# PoppingUnit.net
KiCad netlist of a schematic drawn in EAGLE
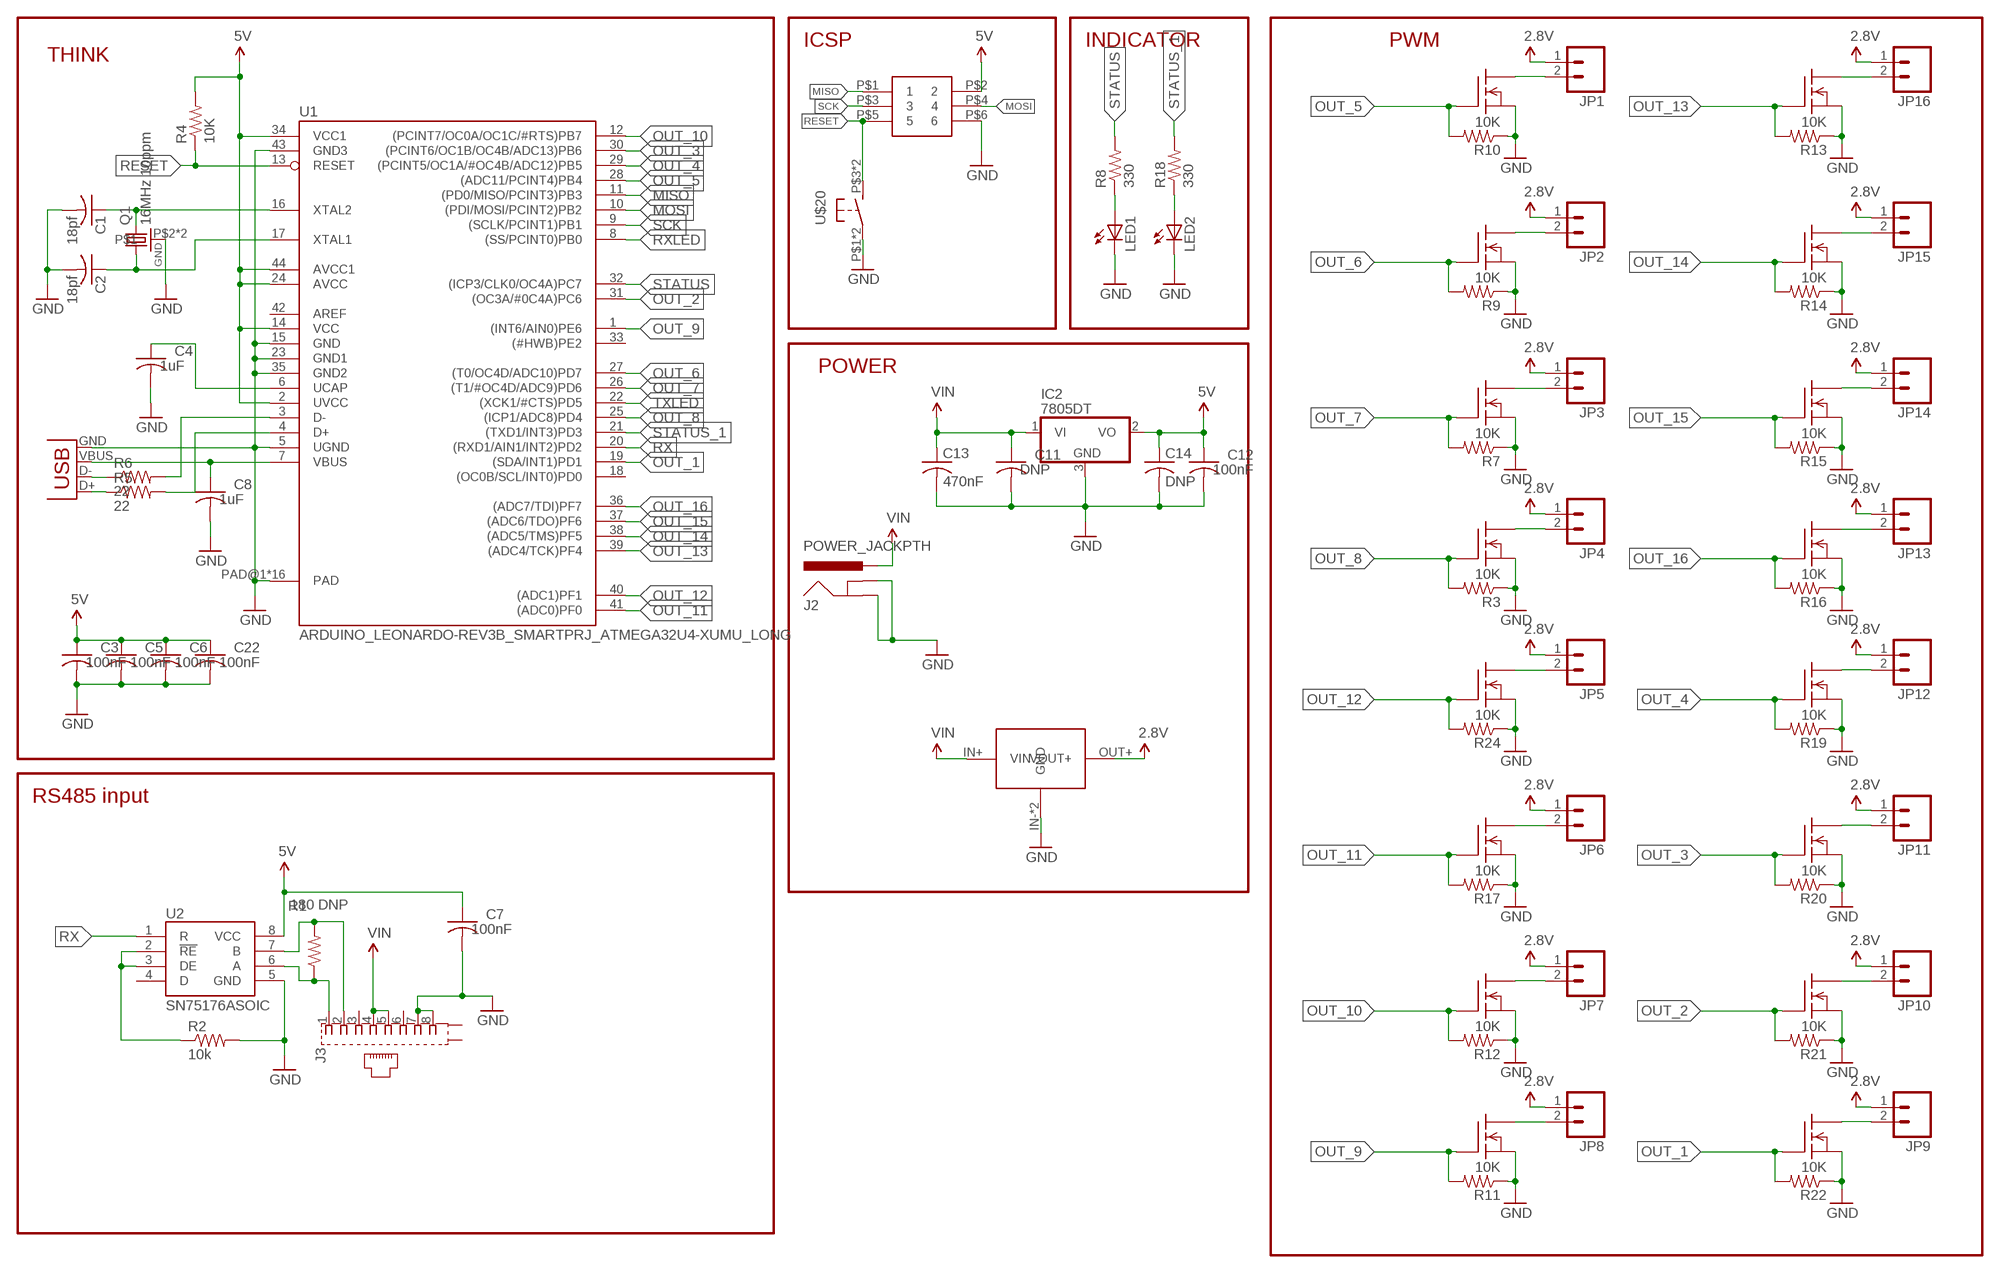
[diagram p0: schematic, sheet 1]

(export (version "E")
  (design (tool "Eeschema 10.0.6"))
  (components
    (comp (ref "C1")
      (value "18pf")
      (footprint "eagle-import:C0603K")
      (libsource (lib "eagle-import") (part "C-USC0603K"))
    )
    (comp (ref "C2")
      (value "18pf")
      (footprint "eagle-import:C0603K")
      (libsource (lib "eagle-import") (part "C-USC0603K"))
    )
    (comp (ref "C3")
      (value "100nF")
      (footprint "eagle-import:C0603K")
      (libsource (lib "eagle-import") (part "C-USC0603K"))
    )
    (comp (ref "C4")
      (value "1uF")
      (footprint "eagle-import:C0603K")
      (libsource (lib "eagle-import") (part "C-USC0603K"))
    )
    (comp (ref "C5")
      (value "100nF")
      (footprint "eagle-import:C0603K")
      (libsource (lib "eagle-import") (part "C-USC0603K"))
    )
    (comp (ref "C6")
      (value "100nF")
      (footprint "eagle-import:C0603K")
      (libsource (lib "eagle-import") (part "C-USC0603K"))
    )
    (comp (ref "C7")
      (value "100nF")
      (footprint "eagle-import:C0603K")
      (libsource (lib "eagle-import") (part "C-USC0603K"))
    )
    (comp (ref "C8")
      (value "1uF")
      (footprint "eagle-import:C0603K")
      (libsource (lib "eagle-import") (part "C-USC0603K"))
    )
    (comp (ref "C11")
      (value "DNP")
      (footprint "eagle-import:C0603K")
      (libsource (lib "eagle-import") (part "C-USC0603K"))
    )
    (comp (ref "C12")
      (value "100nF")
      (footprint "eagle-import:C0603K")
      (libsource (lib "eagle-import") (part "C-USC0603K"))
    )
    (comp (ref "C13")
      (value "470nF")
      (footprint "eagle-import:C0603K")
      (libsource (lib "eagle-import") (part "C-USC0603K"))
    )
    (comp (ref "C14")
      (value "DNP")
      (footprint "eagle-import:C0603K")
      (libsource (lib "eagle-import") (part "C-USC0603K"))
    )
    (comp (ref "C22")
      (value "100nF")
      (footprint "eagle-import:C0603K")
      (libsource (lib "eagle-import") (part "C-USC0603K"))
    )
    (comp (ref "IC2")
      (value "7805DT")
      (footprint "eagle-import:TO252")
      (libsource (lib "eagle-import") (part "78DT05"))
    )
    (comp (ref "J2")
      (value "POWER_JACKPTH")
      (footprint "eagle-import:POWER_JACK_PTH")
      (libsource (lib "eagle-import") (part "POWER_JACKPTH"))
    )
    (comp (ref "J3")
      (value "555153-1")
      (footprint "eagle-import:555153-1")
      (libsource (lib "eagle-import") (part "555153-1"))
    )
    (comp (ref "JP1")
      (value "M02-JST-2-PTH-NO_SILK")
      (footprint "eagle-import:JST-2-PTH-NS")
      (libsource (lib "eagle-import") (part "M02-JST-2-PTH-NO_SILK"))
    )
    (comp (ref "JP2")
      (value "M02-JST-2-PTH-NO_SILK")
      (footprint "eagle-import:JST-2-PTH-NS")
      (libsource (lib "eagle-import") (part "M02-JST-2-PTH-NO_SILK"))
    )
    (comp (ref "JP3")
      (value "M02-JST-2-PTH-NO_SILK")
      (footprint "eagle-import:JST-2-PTH-NS")
      (libsource (lib "eagle-import") (part "M02-JST-2-PTH-NO_SILK"))
    )
    (comp (ref "JP4")
      (value "M02-JST-2-PTH-NO_SILK")
      (footprint "eagle-import:JST-2-PTH-NS")
      (libsource (lib "eagle-import") (part "M02-JST-2-PTH-NO_SILK"))
    )
    (comp (ref "JP5")
      (value "M02-JST-2-PTH-NO_SILK")
      (footprint "eagle-import:JST-2-PTH-NS")
      (libsource (lib "eagle-import") (part "M02-JST-2-PTH-NO_SILK"))
    )
    (comp (ref "JP6")
      (value "M02-JST-2-PTH-NO_SILK")
      (footprint "eagle-import:JST-2-PTH-NS")
      (libsource (lib "eagle-import") (part "M02-JST-2-PTH-NO_SILK"))
    )
    (comp (ref "JP7")
      (value "M02-JST-2-PTH-NO_SILK")
      (footprint "eagle-import:JST-2-PTH-NS")
      (libsource (lib "eagle-import") (part "M02-JST-2-PTH-NO_SILK"))
    )
    (comp (ref "JP8")
      (value "M02-JST-2-PTH-NO_SILK")
      (footprint "eagle-import:JST-2-PTH-NS")
      (libsource (lib "eagle-import") (part "M02-JST-2-PTH-NO_SILK"))
    )
    (comp (ref "JP9")
      (value "M02-JST-2-PTH-NO_SILK")
      (footprint "eagle-import:JST-2-PTH-NS")
      (libsource (lib "eagle-import") (part "M02-JST-2-PTH-NO_SILK"))
    )
    (comp (ref "JP10")
      (value "M02-JST-2-PTH-NO_SILK")
      (footprint "eagle-import:JST-2-PTH-NS")
      (libsource (lib "eagle-import") (part "M02-JST-2-PTH-NO_SILK"))
    )
    (comp (ref "JP11")
      (value "M02-JST-2-PTH-NO_SILK")
      (footprint "eagle-import:JST-2-PTH-NS")
      (libsource (lib "eagle-import") (part "M02-JST-2-PTH-NO_SILK"))
    )
    (comp (ref "JP12")
      (value "M02-JST-2-PTH-NO_SILK")
      (footprint "eagle-import:JST-2-PTH-NS")
      (libsource (lib "eagle-import") (part "M02-JST-2-PTH-NO_SILK"))
    )
    (comp (ref "JP13")
      (value "M02-JST-2-PTH-NO_SILK")
      (footprint "eagle-import:JST-2-PTH-NS")
      (libsource (lib "eagle-import") (part "M02-JST-2-PTH-NO_SILK"))
    )
    (comp (ref "JP14")
      (value "M02-JST-2-PTH-NO_SILK")
      (footprint "eagle-import:JST-2-PTH-NS")
      (libsource (lib "eagle-import") (part "M02-JST-2-PTH-NO_SILK"))
    )
    (comp (ref "JP15")
      (value "M02-JST-2-PTH-NO_SILK")
      (footprint "eagle-import:JST-2-PTH-NS")
      (libsource (lib "eagle-import") (part "M02-JST-2-PTH-NO_SILK"))
    )
    (comp (ref "JP16")
      (value "M02-JST-2-PTH-NO_SILK")
      (footprint "eagle-import:JST-2-PTH-NS")
      (libsource (lib "eagle-import") (part "M02-JST-2-PTH-NO_SILK"))
    )
    (comp (ref "LED1")
      (value "LED5MM")
      (footprint "eagle-import:LED5MM")
      (libsource (lib "eagle-import") (part "LED5MM"))
    )
    (comp (ref "LED2")
      (value "LED5MM")
      (footprint "eagle-import:LED5MM")
      (libsource (lib "eagle-import") (part "LED5MM"))
    )
    (comp (ref "Q1")
      (value "16MHz 10ppm")
      (footprint "eagle-import:CRSYTAL_2520")
      (libsource (lib "eagle-import") (part "CRYSTAL_4PAD2520"))
    )
    (comp (ref "R1")
      (value "180 DNP")
      (footprint "eagle-import:R0603")
      (libsource (lib "eagle-import") (part "R-US_R0603"))
    )
    (comp (ref "R2")
      (value "10k")
      (footprint "eagle-import:R0603")
      (libsource (lib "eagle-import") (part "R-US_R0603"))
    )
    (comp (ref "R3")
      (value "10K")
      (footprint "eagle-import:R0603")
      (libsource (lib "eagle-import") (part "R-US_R0603"))
    )
    (comp (ref "R4")
      (value "10K")
      (footprint "eagle-import:R0603")
      (libsource (lib "eagle-import") (part "R-US_R0603"))
    )
    (comp (ref "R5")
      (value "22")
      (footprint "eagle-import:R0603")
      (libsource (lib "eagle-import") (part "R-US_R0603"))
    )
    (comp (ref "R6")
      (value "22")
      (footprint "eagle-import:R0603")
      (libsource (lib "eagle-import") (part "R-US_R0603"))
    )
    (comp (ref "R7")
      (value "10K")
      (footprint "eagle-import:R0603")
      (libsource (lib "eagle-import") (part "R-US_R0603"))
    )
    (comp (ref "R8")
      (value "330")
      (footprint "eagle-import:R0603")
      (libsource (lib "eagle-import") (part "R-US_R0603"))
    )
    (comp (ref "R9")
      (value "10K")
      (footprint "eagle-import:R0603")
      (libsource (lib "eagle-import") (part "R-US_R0603"))
    )
    (comp (ref "R10")
      (value "10K")
      (footprint "eagle-import:R0603")
      (libsource (lib "eagle-import") (part "R-US_R0603"))
    )
    (comp (ref "R11")
      (value "10K")
      (footprint "eagle-import:R0603")
      (libsource (lib "eagle-import") (part "R-US_R0603"))
    )
    (comp (ref "R12")
      (value "10K")
      (footprint "eagle-import:R0603")
      (libsource (lib "eagle-import") (part "R-US_R0603"))
    )
    (comp (ref "R13")
      (value "10K")
      (footprint "eagle-import:R0603")
      (libsource (lib "eagle-import") (part "R-US_R0603"))
    )
    (comp (ref "R14")
      (value "10K")
      (footprint "eagle-import:R0603")
      (libsource (lib "eagle-import") (part "R-US_R0603"))
    )
    (comp (ref "R15")
      (value "10K")
      (footprint "eagle-import:R0603")
      (libsource (lib "eagle-import") (part "R-US_R0603"))
    )
    (comp (ref "R16")
      (value "10K")
      (footprint "eagle-import:R0603")
      (libsource (lib "eagle-import") (part "R-US_R0603"))
    )
    (comp (ref "R17")
      (value "10K")
      (footprint "eagle-import:R0603")
      (libsource (lib "eagle-import") (part "R-US_R0603"))
    )
    (comp (ref "R18")
      (value "330")
      (footprint "eagle-import:R0603")
      (libsource (lib "eagle-import") (part "R-US_R0603"))
    )
    (comp (ref "R19")
      (value "10K")
      (footprint "eagle-import:R0603")
      (libsource (lib "eagle-import") (part "R-US_R0603"))
    )
    (comp (ref "R20")
      (value "10K")
      (footprint "eagle-import:R0603")
      (libsource (lib "eagle-import") (part "R-US_R0603"))
    )
    (comp (ref "R21")
      (value "10K")
      (footprint "eagle-import:R0603")
      (libsource (lib "eagle-import") (part "R-US_R0603"))
    )
    (comp (ref "R22")
      (value "10K")
      (footprint "eagle-import:R0603")
      (libsource (lib "eagle-import") (part "R-US_R0603"))
    )
    (comp (ref "R24")
      (value "10K")
      (footprint "eagle-import:R0603")
      (libsource (lib "eagle-import") (part "R-US_R0603"))
    )
    (comp (ref "U$1")
      (value "N_MOSFET")
      (footprint "eagle-import:TO252")
      (libsource (lib "eagle-import") (part "N_MOSFET"))
    )
    (comp (ref "U$2")
      (value "2X3HEADER")
      (footprint "eagle-import:2X3HEADER")
      (libsource (lib "eagle-import") (part "2X3HEADER"))
    )
    (comp (ref "U$3")
      (value "N_MOSFET")
      (footprint "eagle-import:TO252")
      (libsource (lib "eagle-import") (part "N_MOSFET"))
    )
    (comp (ref "U$4")
      (value "N_MOSFET")
      (footprint "eagle-import:TO252")
      (libsource (lib "eagle-import") (part "N_MOSFET"))
    )
    (comp (ref "U$5")
      (value "N_MOSFET")
      (footprint "eagle-import:TO252")
      (libsource (lib "eagle-import") (part "N_MOSFET"))
    )
    (comp (ref "U$6")
      (value "N_MOSFET")
      (footprint "eagle-import:TO252")
      (libsource (lib "eagle-import") (part "N_MOSFET"))
    )
    (comp (ref "U$7")
      (value "N_MOSFET")
      (footprint "eagle-import:TO252")
      (libsource (lib "eagle-import") (part "N_MOSFET"))
    )
    (comp (ref "U$8")
      (value "N_MOSFET")
      (footprint "eagle-import:TO252")
      (libsource (lib "eagle-import") (part "N_MOSFET"))
    )
    (comp (ref "U$9")
      (value "N_MOSFET")
      (footprint "eagle-import:TO252")
      (libsource (lib "eagle-import") (part "N_MOSFET"))
    )
    (comp (ref "U$10")
      (value "N_MOSFET")
      (footprint "eagle-import:TO252")
      (libsource (lib "eagle-import") (part "N_MOSFET"))
    )
    (comp (ref "U$11")
      (value "N_MOSFET")
      (footprint "eagle-import:TO252")
      (libsource (lib "eagle-import") (part "N_MOSFET"))
    )
    (comp (ref "U$12")
      (value "N_MOSFET")
      (footprint "eagle-import:TO252")
      (libsource (lib "eagle-import") (part "N_MOSFET"))
    )
    (comp (ref "U$14")
      (value "N_MOSFET")
      (footprint "eagle-import:TO252")
      (libsource (lib "eagle-import") (part "N_MOSFET"))
    )
    (comp (ref "U$15")
      (value "N_MOSFET")
      (footprint "eagle-import:TO252")
      (libsource (lib "eagle-import") (part "N_MOSFET"))
    )
    (comp (ref "U$16")
      (value "N_MOSFET")
      (footprint "eagle-import:TO252")
      (libsource (lib "eagle-import") (part "N_MOSFET"))
    )
    (comp (ref "U$17")
      (value "N_MOSFET")
      (footprint "eagle-import:TO252")
      (libsource (lib "eagle-import") (part "N_MOSFET"))
    )
    (comp (ref "U$18")
      (value "N_MOSFET")
      (footprint "eagle-import:TO252")
      (libsource (lib "eagle-import") (part "N_MOSFET"))
    )
    (comp (ref "U$19")
      (value "DC_DC")
      (footprint "eagle-import:DSN2596")
      (libsource (lib "eagle-import") (part "DC_DC"))
    )
    (comp (ref "U$20")
      (value "BUTTON_MOMENTARY")
      (footprint "eagle-import:BUTTON_MOMENTARY_KMR211G")
      (libsource (lib "eagle-import") (part "BUTTON_MOMENTARY"))
    )
    (comp (ref "U1")
      (value "ARDUINO_LEONARDO-REV3B_SMARTPRJ_ATMEGA32U4-XUMU_LONG")
      (footprint "eagle-import:QFN44ML7X7_LONGLEADS")
      (libsource (lib "eagle-import") (part "ARDUINO_LEONARDO-REV3B_SMARTPRJ_ATMEGA32U4-XUMU_LONG"))
    )
    (comp (ref "U2")
      (value "SN75176ASOIC")
      (footprint "eagle-import:SO08")
      (libsource (lib "eagle-import") (part "SN75176ASOIC"))
    )
    (comp (ref "X1")
      (value "USBPTH")
      (footprint "eagle-import:USB-B-PTH")
      (libsource (lib "eagle-import") (part "USBPTH"))
    )
  )
  (nets
    (net (code "1") (name "/AREF") (class "Default")
      (node (ref "U1") (pin "42") (pinfunction "AREF_42") (pintype "power_in"))
    )
    (net (code "2") (name "2.8V") (class "Default")
      (node (ref "JP1") (pin "1") (pinfunction "1_1") (pintype "passive"))
      (node (ref "JP10") (pin "1") (pinfunction "1_1") (pintype "passive"))
      (node (ref "JP11") (pin "1") (pinfunction "1_1") (pintype "passive"))
      (node (ref "JP12") (pin "1") (pinfunction "1_1") (pintype "passive"))
      (node (ref "JP13") (pin "1") (pinfunction "1_1") (pintype "passive"))
      (node (ref "JP14") (pin "1") (pinfunction "1_1") (pintype "passive"))
      (node (ref "JP15") (pin "1") (pinfunction "1_1") (pintype "passive"))
      (node (ref "JP16") (pin "1") (pinfunction "1_1") (pintype "passive"))
      (node (ref "JP2") (pin "1") (pinfunction "1_1") (pintype "passive"))
      (node (ref "JP3") (pin "1") (pinfunction "1_1") (pintype "passive"))
      (node (ref "JP4") (pin "1") (pinfunction "1_1") (pintype "passive"))
      (node (ref "JP5") (pin "1") (pinfunction "1_1") (pintype "passive"))
      (node (ref "JP6") (pin "1") (pinfunction "1_1") (pintype "passive"))
      (node (ref "JP7") (pin "1") (pinfunction "1_1") (pintype "passive"))
      (node (ref "JP8") (pin "1") (pinfunction "1_1") (pintype "passive"))
      (node (ref "JP9") (pin "1") (pinfunction "1_1") (pintype "passive"))
      (node (ref "U$19") (pin "OUT+") (pinfunction "VOUT+_OUT+") (pintype "power_in"))
    )
    (net (code "3") (name "5V") (class "Default")
      (node (ref "C12") (pin "1") (pinfunction "1_1") (pintype "passive"))
      (node (ref "C14") (pin "1") (pinfunction "1_1") (pintype "passive"))
      (node (ref "C22") (pin "1") (pinfunction "1_1") (pintype "passive"))
      (node (ref "C3") (pin "1") (pinfunction "1_1") (pintype "passive"))
      (node (ref "C5") (pin "1") (pinfunction "1_1") (pintype "passive"))
      (node (ref "C6") (pin "1") (pinfunction "1_1") (pintype "passive"))
      (node (ref "C7") (pin "1") (pinfunction "1_1") (pintype "passive"))
      (node (ref "IC2") (pin "2") (pinfunction "VO_2") (pintype "passive"))
      (node (ref "R4") (pin "2") (pinfunction "2_2") (pintype "passive"))
      (node (ref "U$2") (pin "P$2") (pinfunction "2_P$2") (pintype "bidirectional"))
      (node (ref "U1") (pin "14") (pinfunction "VCC_14") (pintype "power_in"))
      (node (ref "U1") (pin "2") (pinfunction "UVCC_2") (pintype "power_in"))
      (node (ref "U1") (pin "24") (pinfunction "AVCC_24") (pintype "power_in"))
      (node (ref "U1") (pin "34") (pinfunction "VCC1_34") (pintype "power_in"))
      (node (ref "U1") (pin "44") (pinfunction "AVCC1_44") (pintype "power_in"))
      (node (ref "U2") (pin "8") (pinfunction "VCC_8") (pintype "bidirectional"))
    )
    (net (code "4") (name "GND") (class "Default")
      (node (ref "C1") (pin "2") (pinfunction "2_2") (pintype "passive"))
      (node (ref "C11") (pin "2") (pinfunction "2_2") (pintype "passive"))
      (node (ref "C12") (pin "2") (pinfunction "2_2") (pintype "passive"))
      (node (ref "C13") (pin "2") (pinfunction "2_2") (pintype "passive"))
      (node (ref "C14") (pin "2") (pinfunction "2_2") (pintype "passive"))
      (node (ref "C2") (pin "2") (pinfunction "2_2") (pintype "passive"))
      (node (ref "C22") (pin "2") (pinfunction "2_2") (pintype "passive"))
      (node (ref "C3") (pin "2") (pinfunction "2_2") (pintype "passive"))
      (node (ref "C4") (pin "2") (pinfunction "2_2") (pintype "passive"))
      (node (ref "C5") (pin "2") (pinfunction "2_2") (pintype "passive"))
      (node (ref "C6") (pin "2") (pinfunction "2_2") (pintype "passive"))
      (node (ref "C7") (pin "2") (pinfunction "2_2") (pintype "passive"))
      (node (ref "C8") (pin "2") (pinfunction "2_2") (pintype "passive"))
      (node (ref "IC2") (pin "3") (pinfunction "GND_3") (pintype "passive"))
      (node (ref "J2") (pin "GND") (pinfunction "GND_GND") (pintype "bidirectional"))
      (node (ref "J2") (pin "GNDBREAK") (pinfunction "GNDBREAK_GNDBREAK") (pintype "bidirectional"))
      (node (ref "J3") (pin "7") (pinfunction "7_7") (pintype "passive"))
      (node (ref "J3") (pin "8") (pinfunction "8_8") (pintype "passive"))
      (node (ref "LED1") (pin "K") (pinfunction "C_K") (pintype "passive"))
      (node (ref "LED2") (pin "K") (pinfunction "C_K") (pintype "passive"))
      (node (ref "Q1") (pin "P$2") (pinfunction "P$1_P$2") (pintype "bidirectional"))
      (node (ref "Q1") (pin "P$4") (pinfunction "P$1_P$4") (pintype "bidirectional"))
      (node (ref "R10") (pin "1") (pinfunction "1_1") (pintype "passive"))
      (node (ref "R11") (pin "1") (pinfunction "1_1") (pintype "passive"))
      (node (ref "R12") (pin "1") (pinfunction "1_1") (pintype "passive"))
      (node (ref "R13") (pin "1") (pinfunction "1_1") (pintype "passive"))
      (node (ref "R14") (pin "1") (pinfunction "1_1") (pintype "passive"))
      (node (ref "R15") (pin "1") (pinfunction "1_1") (pintype "passive"))
      (node (ref "R16") (pin "1") (pinfunction "1_1") (pintype "passive"))
      (node (ref "R17") (pin "1") (pinfunction "1_1") (pintype "passive"))
      (node (ref "R19") (pin "1") (pinfunction "1_1") (pintype "passive"))
      (node (ref "R2") (pin "2") (pinfunction "2_2") (pintype "passive"))
      (node (ref "R20") (pin "1") (pinfunction "1_1") (pintype "passive"))
      (node (ref "R21") (pin "1") (pinfunction "1_1") (pintype "passive"))
      (node (ref "R22") (pin "1") (pinfunction "1_1") (pintype "passive"))
      (node (ref "R24") (pin "1") (pinfunction "1_1") (pintype "passive"))
      (node (ref "R3") (pin "1") (pinfunction "1_1") (pintype "passive"))
      (node (ref "R7") (pin "1") (pinfunction "1_1") (pintype "passive"))
      (node (ref "R9") (pin "1") (pinfunction "1_1") (pintype "passive"))
      (node (ref "U$1") (pin "P$2") (pinfunction "S_P$2") (pintype "bidirectional"))
      (node (ref "U$10") (pin "P$2") (pinfunction "S_P$2") (pintype "bidirectional"))
      (node (ref "U$11") (pin "P$2") (pinfunction "S_P$2") (pintype "bidirectional"))
      (node (ref "U$12") (pin "P$2") (pinfunction "S_P$2") (pintype "bidirectional"))
      (node (ref "U$14") (pin "P$2") (pinfunction "S_P$2") (pintype "bidirectional"))
      (node (ref "U$15") (pin "P$2") (pinfunction "S_P$2") (pintype "bidirectional"))
      (node (ref "U$16") (pin "P$2") (pinfunction "S_P$2") (pintype "bidirectional"))
      (node (ref "U$17") (pin "P$2") (pinfunction "S_P$2") (pintype "bidirectional"))
      (node (ref "U$18") (pin "P$2") (pinfunction "S_P$2") (pintype "bidirectional"))
      (node (ref "U$19") (pin "IN-") (pinfunction "GND_IN-") (pintype "power_in"))
      (node (ref "U$19") (pin "OUT-") (pinfunction "GND_OUT-") (pintype "power_in"))
      (node (ref "U$2") (pin "P$6") (pinfunction "6_P$6") (pintype "bidirectional"))
      (node (ref "U$20") (pin "P$1") (pinfunction "P_P$1") (pintype "passive"))
      (node (ref "U$20") (pin "P$2") (pinfunction "P_P$2") (pintype "passive"))
      (node (ref "U$3") (pin "P$2") (pinfunction "S_P$2") (pintype "bidirectional"))
      (node (ref "U$4") (pin "P$2") (pinfunction "S_P$2") (pintype "bidirectional"))
      (node (ref "U$5") (pin "P$2") (pinfunction "S_P$2") (pintype "bidirectional"))
      (node (ref "U$6") (pin "P$2") (pinfunction "S_P$2") (pintype "bidirectional"))
      (node (ref "U$7") (pin "P$2") (pinfunction "S_P$2") (pintype "bidirectional"))
      (node (ref "U$8") (pin "P$2") (pinfunction "S_P$2") (pintype "bidirectional"))
      (node (ref "U$9") (pin "P$2") (pinfunction "S_P$2") (pintype "bidirectional"))
      (node (ref "U1") (pin "15") (pinfunction "GND_15") (pintype "power_in"))
      (node (ref "U1") (pin "23") (pinfunction "GND1_23") (pintype "power_in"))
      (node (ref "U1") (pin "35") (pinfunction "GND2_35") (pintype "power_in"))
      (node (ref "U1") (pin "43") (pinfunction "GND3_43") (pintype "power_in"))
      (node (ref "U1") (pin "5") (pinfunction "UGND_5") (pintype "power_in"))
      (node (ref "U1") (pin "PAD@1") (pinfunction "PAD_PAD@1") (pintype "power_in"))
      (node (ref "U1") (pin "PAD@10") (pinfunction "PAD_PAD@10") (pintype "power_in"))
      (node (ref "U1") (pin "PAD@11") (pinfunction "PAD_PAD@11") (pintype "power_in"))
      (node (ref "U1") (pin "PAD@12") (pinfunction "PAD_PAD@12") (pintype "power_in"))
      (node (ref "U1") (pin "PAD@13") (pinfunction "PAD_PAD@13") (pintype "power_in"))
      (node (ref "U1") (pin "PAD@14") (pinfunction "PAD_PAD@14") (pintype "power_in"))
      (node (ref "U1") (pin "PAD@15") (pinfunction "PAD_PAD@15") (pintype "power_in"))
      (node (ref "U1") (pin "PAD@16") (pinfunction "PAD_PAD@16") (pintype "power_in"))
      (node (ref "U1") (pin "PAD@2") (pinfunction "PAD_PAD@2") (pintype "power_in"))
      (node (ref "U1") (pin "PAD@3") (pinfunction "PAD_PAD@3") (pintype "power_in"))
      (node (ref "U1") (pin "PAD@4") (pinfunction "PAD_PAD@4") (pintype "power_in"))
      (node (ref "U1") (pin "PAD@5") (pinfunction "PAD_PAD@5") (pintype "power_in"))
      (node (ref "U1") (pin "PAD@6") (pinfunction "PAD_PAD@6") (pintype "power_in"))
      (node (ref "U1") (pin "PAD@7") (pinfunction "PAD_PAD@7") (pintype "power_in"))
      (node (ref "U1") (pin "PAD@8") (pinfunction "PAD_PAD@8") (pintype "power_in"))
      (node (ref "U1") (pin "PAD@9") (pinfunction "PAD_PAD@9") (pintype "power_in"))
      (node (ref "U2") (pin "5") (pinfunction "GND_5") (pintype "bidirectional"))
      (node (ref "X1") (pin "GND") (pinfunction "GND_GND") (pintype "bidirectional"))
    )
    (net (code "5") (name "MISO") (class "Default")
      (node (ref "U$2") (pin "P$1") (pinfunction "1_P$1") (pintype "bidirectional"))
      (node (ref "U1") (pin "11") (pinfunction "(PD0/MISO/PCINT3)PB3_11") (pintype "bidirectional"))
    )
    (net (code "6") (name "MOSI") (class "Default")
      (node (ref "U$2") (pin "P$4") (pinfunction "4_P$4") (pintype "bidirectional"))
      (node (ref "U1") (pin "10") (pinfunction "(PDI/MOSI/PCINT2)PB2_10") (pintype "bidirectional"))
    )
    (net (code "7") (name "Net-(LED1-PadA)") (class "Default")
      (node (ref "LED1") (pin "A") (pinfunction "A_A") (pintype "passive"))
      (node (ref "R8") (pin "1") (pinfunction "1_1") (pintype "passive"))
    )
    (net (code "8") (name "Net-(LED2-PadA)") (class "Default")
      (node (ref "LED2") (pin "A") (pinfunction "A_A") (pintype "passive"))
      (node (ref "R18") (pin "1") (pinfunction "1_1") (pintype "passive"))
    )
    (net (code "9") (name "Net-(Q1-1)") (class "Default")
      (node (ref "C2") (pin "1") (pinfunction "1_1") (pintype "passive"))
      (node (ref "Q1") (pin "P$1") (pinfunction "1_P$1") (pintype "passive"))
      (node (ref "U1") (pin "17") (pinfunction "XTAL1_17") (pintype "bidirectional"))
    )
    (net (code "10") (name "Net-(Q1-2)") (class "Default")
      (node (ref "C1") (pin "1") (pinfunction "1_1") (pintype "passive"))
      (node (ref "Q1") (pin "P$3") (pinfunction "2_P$3") (pintype "passive"))
      (node (ref "U1") (pin "16") (pinfunction "XTAL2_16") (pintype "bidirectional"))
    )
    (net (code "11") (name "Net-(R5-Pad1)") (class "Default")
      (node (ref "R5") (pin "1") (pinfunction "1_1") (pintype "passive"))
      (node (ref "X1") (pin "D+") (pinfunction "D+_D+") (pintype "bidirectional"))
    )
    (net (code "12") (name "Net-(R6-Pad1)") (class "Default")
      (node (ref "R6") (pin "1") (pinfunction "1_1") (pintype "passive"))
      (node (ref "X1") (pin "D-") (pinfunction "D-_D-") (pintype "bidirectional"))
    )
    (net (code "13") (name "Net-(U$1-D)") (class "Default")
      (node (ref "JP1") (pin "2") (pinfunction "2_2") (pintype "passive"))
      (node (ref "U$1") (pin "P$3") (pinfunction "D_P$3") (pintype "bidirectional"))
    )
    (net (code "14") (name "Net-(U$3-D)") (class "Default")
      (node (ref "JP2") (pin "2") (pinfunction "2_2") (pintype "passive"))
      (node (ref "U$3") (pin "P$3") (pinfunction "D_P$3") (pintype "bidirectional"))
    )
    (net (code "15") (name "Net-(U$4-D)") (class "Default")
      (node (ref "JP3") (pin "2") (pinfunction "2_2") (pintype "passive"))
      (node (ref "U$4") (pin "P$3") (pinfunction "D_P$3") (pintype "bidirectional"))
    )
    (net (code "16") (name "Net-(U$5-D)") (class "Default")
      (node (ref "JP4") (pin "2") (pinfunction "2_2") (pintype "passive"))
      (node (ref "U$5") (pin "P$3") (pinfunction "D_P$3") (pintype "bidirectional"))
    )
    (net (code "17") (name "Net-(U$6-D)") (class "Default")
      (node (ref "JP16") (pin "2") (pinfunction "2_2") (pintype "passive"))
      (node (ref "U$6") (pin "P$3") (pinfunction "D_P$3") (pintype "bidirectional"))
    )
    (net (code "18") (name "Net-(U$7-D)") (class "Default")
      (node (ref "JP15") (pin "2") (pinfunction "2_2") (pintype "passive"))
      (node (ref "U$7") (pin "P$3") (pinfunction "D_P$3") (pintype "bidirectional"))
    )
    (net (code "19") (name "Net-(U$8-D)") (class "Default")
      (node (ref "JP14") (pin "2") (pinfunction "2_2") (pintype "passive"))
      (node (ref "U$8") (pin "P$3") (pinfunction "D_P$3") (pintype "bidirectional"))
    )
    (net (code "20") (name "Net-(U$9-D)") (class "Default")
      (node (ref "JP13") (pin "2") (pinfunction "2_2") (pintype "passive"))
      (node (ref "U$9") (pin "P$3") (pinfunction "D_P$3") (pintype "bidirectional"))
    )
    (net (code "21") (name "Net-(U$10-D)") (class "Default")
      (node (ref "JP5") (pin "2") (pinfunction "2_2") (pintype "passive"))
      (node (ref "U$10") (pin "P$3") (pinfunction "D_P$3") (pintype "bidirectional"))
    )
    (net (code "22") (name "Net-(U$11-D)") (class "Default")
      (node (ref "JP6") (pin "2") (pinfunction "2_2") (pintype "passive"))
      (node (ref "U$11") (pin "P$3") (pinfunction "D_P$3") (pintype "bidirectional"))
    )
    (net (code "23") (name "Net-(U$12-D)") (class "Default")
      (node (ref "JP7") (pin "2") (pinfunction "2_2") (pintype "passive"))
      (node (ref "U$12") (pin "P$3") (pinfunction "D_P$3") (pintype "bidirectional"))
    )
    (net (code "24") (name "Net-(U$14-D)") (class "Default")
      (node (ref "JP8") (pin "2") (pinfunction "2_2") (pintype "passive"))
      (node (ref "U$14") (pin "P$3") (pinfunction "D_P$3") (pintype "bidirectional"))
    )
    (net (code "25") (name "Net-(U$15-D)") (class "Default")
      (node (ref "JP12") (pin "2") (pinfunction "2_2") (pintype "passive"))
      (node (ref "U$15") (pin "P$3") (pinfunction "D_P$3") (pintype "bidirectional"))
    )
    (net (code "26") (name "Net-(U$16-D)") (class "Default")
      (node (ref "JP11") (pin "2") (pinfunction "2_2") (pintype "passive"))
      (node (ref "U$16") (pin "P$3") (pinfunction "D_P$3") (pintype "bidirectional"))
    )
    (net (code "27") (name "Net-(U$17-D)") (class "Default")
      (node (ref "JP10") (pin "2") (pinfunction "2_2") (pintype "passive"))
      (node (ref "U$17") (pin "P$3") (pinfunction "D_P$3") (pintype "bidirectional"))
    )
    (net (code "28") (name "Net-(U$18-D)") (class "Default")
      (node (ref "JP9") (pin "2") (pinfunction "2_2") (pintype "passive"))
      (node (ref "U$18") (pin "P$3") (pinfunction "D_P$3") (pintype "bidirectional"))
    )
    (net (code "29") (name "Net-(U1-D+)") (class "Default")
      (node (ref "R5") (pin "2") (pinfunction "2_2") (pintype "passive"))
      (node (ref "U1") (pin "4") (pinfunction "D+_4") (pintype "bidirectional"))
    )
    (net (code "30") (name "Net-(U1-D-)") (class "Default")
      (node (ref "R6") (pin "2") (pinfunction "2_2") (pintype "passive"))
      (node (ref "U1") (pin "3") (pinfunction "D-_3") (pintype "bidirectional"))
    )
    (net (code "31") (name "Net-(U1-UCAP)") (class "Default")
      (node (ref "C4") (pin "1") (pinfunction "1_1") (pintype "passive"))
      (node (ref "U1") (pin "6") (pinfunction "UCAP_6") (pintype "passive"))
    )
    (net (code "32") (name "Net-(U1-VBUS)") (class "Default")
      (node (ref "C8") (pin "1") (pinfunction "1_1") (pintype "passive"))
      (node (ref "U1") (pin "7") (pinfunction "VBUS_7") (pintype "input"))
      (node (ref "X1") (pin "VBUS") (pinfunction "VBUS_VBUS") (pintype "bidirectional"))
    )
    (net (code "33") (name "Net-(U2-A)") (class "Default")
      (node (ref "J3") (pin "1") (pinfunction "1_1") (pintype "passive"))
      (node (ref "R1") (pin "1") (pinfunction "1_1") (pintype "passive"))
      (node (ref "U2") (pin "6") (pinfunction "A_6") (pintype "bidirectional"))
    )
    (net (code "34") (name "Net-(U2-B)") (class "Default")
      (node (ref "J3") (pin "2") (pinfunction "2_2") (pintype "passive"))
      (node (ref "R1") (pin "2") (pinfunction "2_2") (pintype "passive"))
      (node (ref "U2") (pin "7") (pinfunction "B_7") (pintype "bidirectional"))
    )
    (net (code "35") (name "Net-(U2-DE)") (class "Default")
      (node (ref "R2") (pin "1") (pinfunction "1_1") (pintype "passive"))
      (node (ref "U2") (pin "2") (pinfunction "~{RE}_2") (pintype "bidirectional"))
      (node (ref "U2") (pin "3") (pinfunction "DE_3") (pintype "bidirectional"))
    )
    (net (code "36") (name "OUT_1") (class "Default")
      (node (ref "R22") (pin "2") (pinfunction "2_2") (pintype "passive"))
      (node (ref "U$18") (pin "P$1") (pinfunction "G_P$1") (pintype "bidirectional"))
      (node (ref "U1") (pin "19") (pinfunction "(SDA/INT1)PD1_19") (pintype "bidirectional"))
    )
    (net (code "37") (name "OUT_2") (class "Default")
      (node (ref "R21") (pin "2") (pinfunction "2_2") (pintype "passive"))
      (node (ref "U$17") (pin "P$1") (pinfunction "G_P$1") (pintype "bidirectional"))
      (node (ref "U1") (pin "31") (pinfunction "(OC3A/#0C4A)PC6_31") (pintype "bidirectional"))
    )
    (net (code "38") (name "OUT_3") (class "Default")
      (node (ref "R20") (pin "2") (pinfunction "2_2") (pintype "passive"))
      (node (ref "U$16") (pin "P$1") (pinfunction "G_P$1") (pintype "bidirectional"))
      (node (ref "U1") (pin "30") (pinfunction "(PCINT6/OC1B/OC4B/ADC13)PB6_30") (pintype "bidirectional"))
    )
    (net (code "39") (name "OUT_4") (class "Default")
      (node (ref "R19") (pin "2") (pinfunction "2_2") (pintype "passive"))
      (node (ref "U$15") (pin "P$1") (pinfunction "G_P$1") (pintype "bidirectional"))
      (node (ref "U1") (pin "29") (pinfunction "(PCINT5/OC1A/#OC4B/ADC12)PB5_29") (pintype "bidirectional"))
    )
    (net (code "40") (name "OUT_5") (class "Default")
      (node (ref "R10") (pin "2") (pinfunction "2_2") (pintype "passive"))
      (node (ref "U$1") (pin "P$1") (pinfunction "G_P$1") (pintype "bidirectional"))
      (node (ref "U1") (pin "28") (pinfunction "(ADC11/PCINT4)PB4_28") (pintype "bidirectional"))
    )
    (net (code "41") (name "OUT_6") (class "Default")
      (node (ref "R9") (pin "2") (pinfunction "2_2") (pintype "passive"))
      (node (ref "U$3") (pin "P$1") (pinfunction "G_P$1") (pintype "bidirectional"))
      (node (ref "U1") (pin "27") (pinfunction "(T0/OC4D/ADC10)PD7_27") (pintype "bidirectional"))
    )
    (net (code "42") (name "OUT_7") (class "Default")
      (node (ref "R7") (pin "2") (pinfunction "2_2") (pintype "passive"))
      (node (ref "U$4") (pin "P$1") (pinfunction "G_P$1") (pintype "bidirectional"))
      (node (ref "U1") (pin "26") (pinfunction "(T1/#OC4D/ADC9)PD6_26") (pintype "bidirectional"))
    )
    (net (code "43") (name "OUT_8") (class "Default")
      (node (ref "R3") (pin "2") (pinfunction "2_2") (pintype "passive"))
      (node (ref "U$5") (pin "P$1") (pinfunction "G_P$1") (pintype "bidirectional"))
      (node (ref "U1") (pin "25") (pinfunction "(ICP1/ADC8)PD4_25") (pintype "bidirectional"))
    )
    (net (code "44") (name "OUT_9") (class "Default")
      (node (ref "R11") (pin "2") (pinfunction "2_2") (pintype "passive"))
      (node (ref "U$14") (pin "P$1") (pinfunction "G_P$1") (pintype "bidirectional"))
      (node (ref "U1") (pin "1") (pinfunction "(INT6/AIN0)PE6_1") (pintype "bidirectional"))
    )
    (net (code "45") (name "OUT_10") (class "Default")
      (node (ref "R12") (pin "2") (pinfunction "2_2") (pintype "passive"))
      (node (ref "U$12") (pin "P$1") (pinfunction "G_P$1") (pintype "bidirectional"))
      (node (ref "U1") (pin "12") (pinfunction "(PCINT7/OC0A/OC1C/#RTS)PB7_12") (pintype "bidirectional"))
    )
    (net (code "46") (name "OUT_11") (class "Default")
      (node (ref "R17") (pin "2") (pinfunction "2_2") (pintype "passive"))
      (node (ref "U$11") (pin "P$1") (pinfunction "G_P$1") (pintype "bidirectional"))
      (node (ref "U1") (pin "41") (pinfunction "(ADC0)PF0_41") (pintype "bidirectional"))
    )
    (net (code "47") (name "OUT_12") (class "Default")
      (node (ref "R24") (pin "2") (pinfunction "2_2") (pintype "passive"))
      (node (ref "U$10") (pin "P$1") (pinfunction "G_P$1") (pintype "bidirectional"))
      (node (ref "U1") (pin "40") (pinfunction "(ADC1)PF1_40") (pintype "bidirectional"))
    )
    (net (code "48") (name "OUT_13") (class "Default")
      (node (ref "R13") (pin "2") (pinfunction "2_2") (pintype "passive"))
      (node (ref "U$6") (pin "P$1") (pinfunction "G_P$1") (pintype "bidirectional"))
      (node (ref "U1") (pin "39") (pinfunction "(ADC4/TCK)PF4_39") (pintype "bidirectional"))
    )
    (net (code "49") (name "OUT_14") (class "Default")
      (node (ref "R14") (pin "2") (pinfunction "2_2") (pintype "passive"))
      (node (ref "U$7") (pin "P$1") (pinfunction "G_P$1") (pintype "bidirectional"))
      (node (ref "U1") (pin "38") (pinfunction "(ADC5/TMS)PF5_38") (pintype "bidirectional"))
    )
    (net (code "50") (name "OUT_15") (class "Default")
      (node (ref "R15") (pin "2") (pinfunction "2_2") (pintype "passive"))
      (node (ref "U$8") (pin "P$1") (pinfunction "G_P$1") (pintype "bidirectional"))
      (node (ref "U1") (pin "37") (pinfunction "(ADC6/TDO)PF6_37") (pintype "bidirectional"))
    )
    (net (code "51") (name "OUT_16") (class "Default")
      (node (ref "R16") (pin "2") (pinfunction "2_2") (pintype "passive"))
      (node (ref "U$9") (pin "P$1") (pinfunction "G_P$1") (pintype "bidirectional"))
      (node (ref "U1") (pin "36") (pinfunction "(ADC7/TDI)PF7_36") (pintype "bidirectional"))
    )
    (net (code "52") (name "RESET") (class "Default")
      (node (ref "R4") (pin "1") (pinfunction "1_1") (pintype "passive"))
      (node (ref "U$2") (pin "P$5") (pinfunction "5_P$5") (pintype "bidirectional"))
      (node (ref "U$20") (pin "P$3") (pinfunction "S_P$3") (pintype "passive"))
      (node (ref "U$20") (pin "P$4") (pinfunction "S_P$4") (pintype "passive"))
      (node (ref "U1") (pin "13") (pinfunction "RESET_13") (pintype "input"))
    )
    (net (code "53") (name "RX") (class "Default")
      (node (ref "U1") (pin "20") (pinfunction "(RXD1/AIN1/INT2)PD2_20") (pintype "bidirectional"))
      (node (ref "U2") (pin "1") (pinfunction "R_1") (pintype "bidirectional"))
    )
    (net (code "54") (name "RXLED") (class "Default")
      (node (ref "U1") (pin "8") (pinfunction "(SS/PCINT0)PB0_8") (pintype "bidirectional"))
    )
    (net (code "55") (name "SCK") (class "Default")
      (node (ref "U$2") (pin "P$3") (pinfunction "3_P$3") (pintype "bidirectional"))
      (node (ref "U1") (pin "9") (pinfunction "(SCLK/PCINT1)PB1_9") (pintype "bidirectional"))
    )
    (net (code "56") (name "STATUS") (class "Default")
      (node (ref "R8") (pin "2") (pinfunction "2_2") (pintype "passive"))
      (node (ref "U1") (pin "32") (pinfunction "(ICP3/CLK0/OC4A)PC7_32") (pintype "bidirectional"))
    )
    (net (code "57") (name "STATUS_1") (class "Default")
      (node (ref "R18") (pin "2") (pinfunction "2_2") (pintype "passive"))
      (node (ref "U1") (pin "21") (pinfunction "(TXD1/INT3)PD3_21") (pintype "bidirectional"))
    )
    (net (code "58") (name "TXLED") (class "Default")
      (node (ref "U1") (pin "22") (pinfunction "(XCK1/#CTS)PD5_22") (pintype "bidirectional"))
    )
    (net (code "59") (name "VIN") (class "Default")
      (node (ref "C11") (pin "1") (pinfunction "1_1") (pintype "passive"))
      (node (ref "C13") (pin "1") (pinfunction "1_1") (pintype "passive"))
      (node (ref "IC2") (pin "1") (pinfunction "VI_1") (pintype "input"))
      (node (ref "J2") (pin "PWR") (pinfunction "PWR_PWR") (pintype "bidirectional"))
      (node (ref "J3") (pin "4") (pinfunction "4_4") (pintype "passive"))
      (node (ref "J3") (pin "5") (pinfunction "5_5") (pintype "passive"))
      (node (ref "U$19") (pin "IN+") (pinfunction "VIN_IN+") (pintype "power_in"))
    )
    (net (code "60") (name "unconnected-(J3-Pad3)") (class "Default")
      (node (ref "J3") (pin "3") (pinfunction "3_3") (pintype "passive"))
    )
    (net (code "61") (name "unconnected-(J3-Pad6)") (class "Default")
      (node (ref "J3") (pin "6") (pinfunction "6_6") (pintype "passive"))
    )
    (net (code "62") (name "unconnected-(J3-S1-PadG1)") (class "Default")
      (node (ref "J3") (pin "G1") (pinfunction "S1_G1") (pintype "passive"))
    )
    (net (code "63") (name "unconnected-(J3-S2-PadG2)") (class "Default")
      (node (ref "J3") (pin "G2") (pinfunction "S2_G2") (pintype "passive"))
    )
    (net (code "64") (name "unconnected-(U1-(#HWB)PE2-Pad33)") (class "Default")
      (node (ref "U1") (pin "33") (pinfunction "(#HWB)PE2_33") (pintype "bidirectional"))
    )
    (net (code "65") (name "unconnected-(U1-(OC0B{slash}SCL{slash}INT0)PD0-Pad18)") (class "Default")
      (node (ref "U1") (pin "18") (pinfunction "(OC0B/SCL/INT0)PD0_18") (pintype "bidirectional"))
    )
    (net (code "66") (name "unconnected-(U2-D-Pad4)") (class "Default")
      (node (ref "U2") (pin "4") (pinfunction "D_4") (pintype "bidirectional"))
    )
  )
)
